# Esquema.net
KiCad netlist of a schematic drawn in Altium Designer
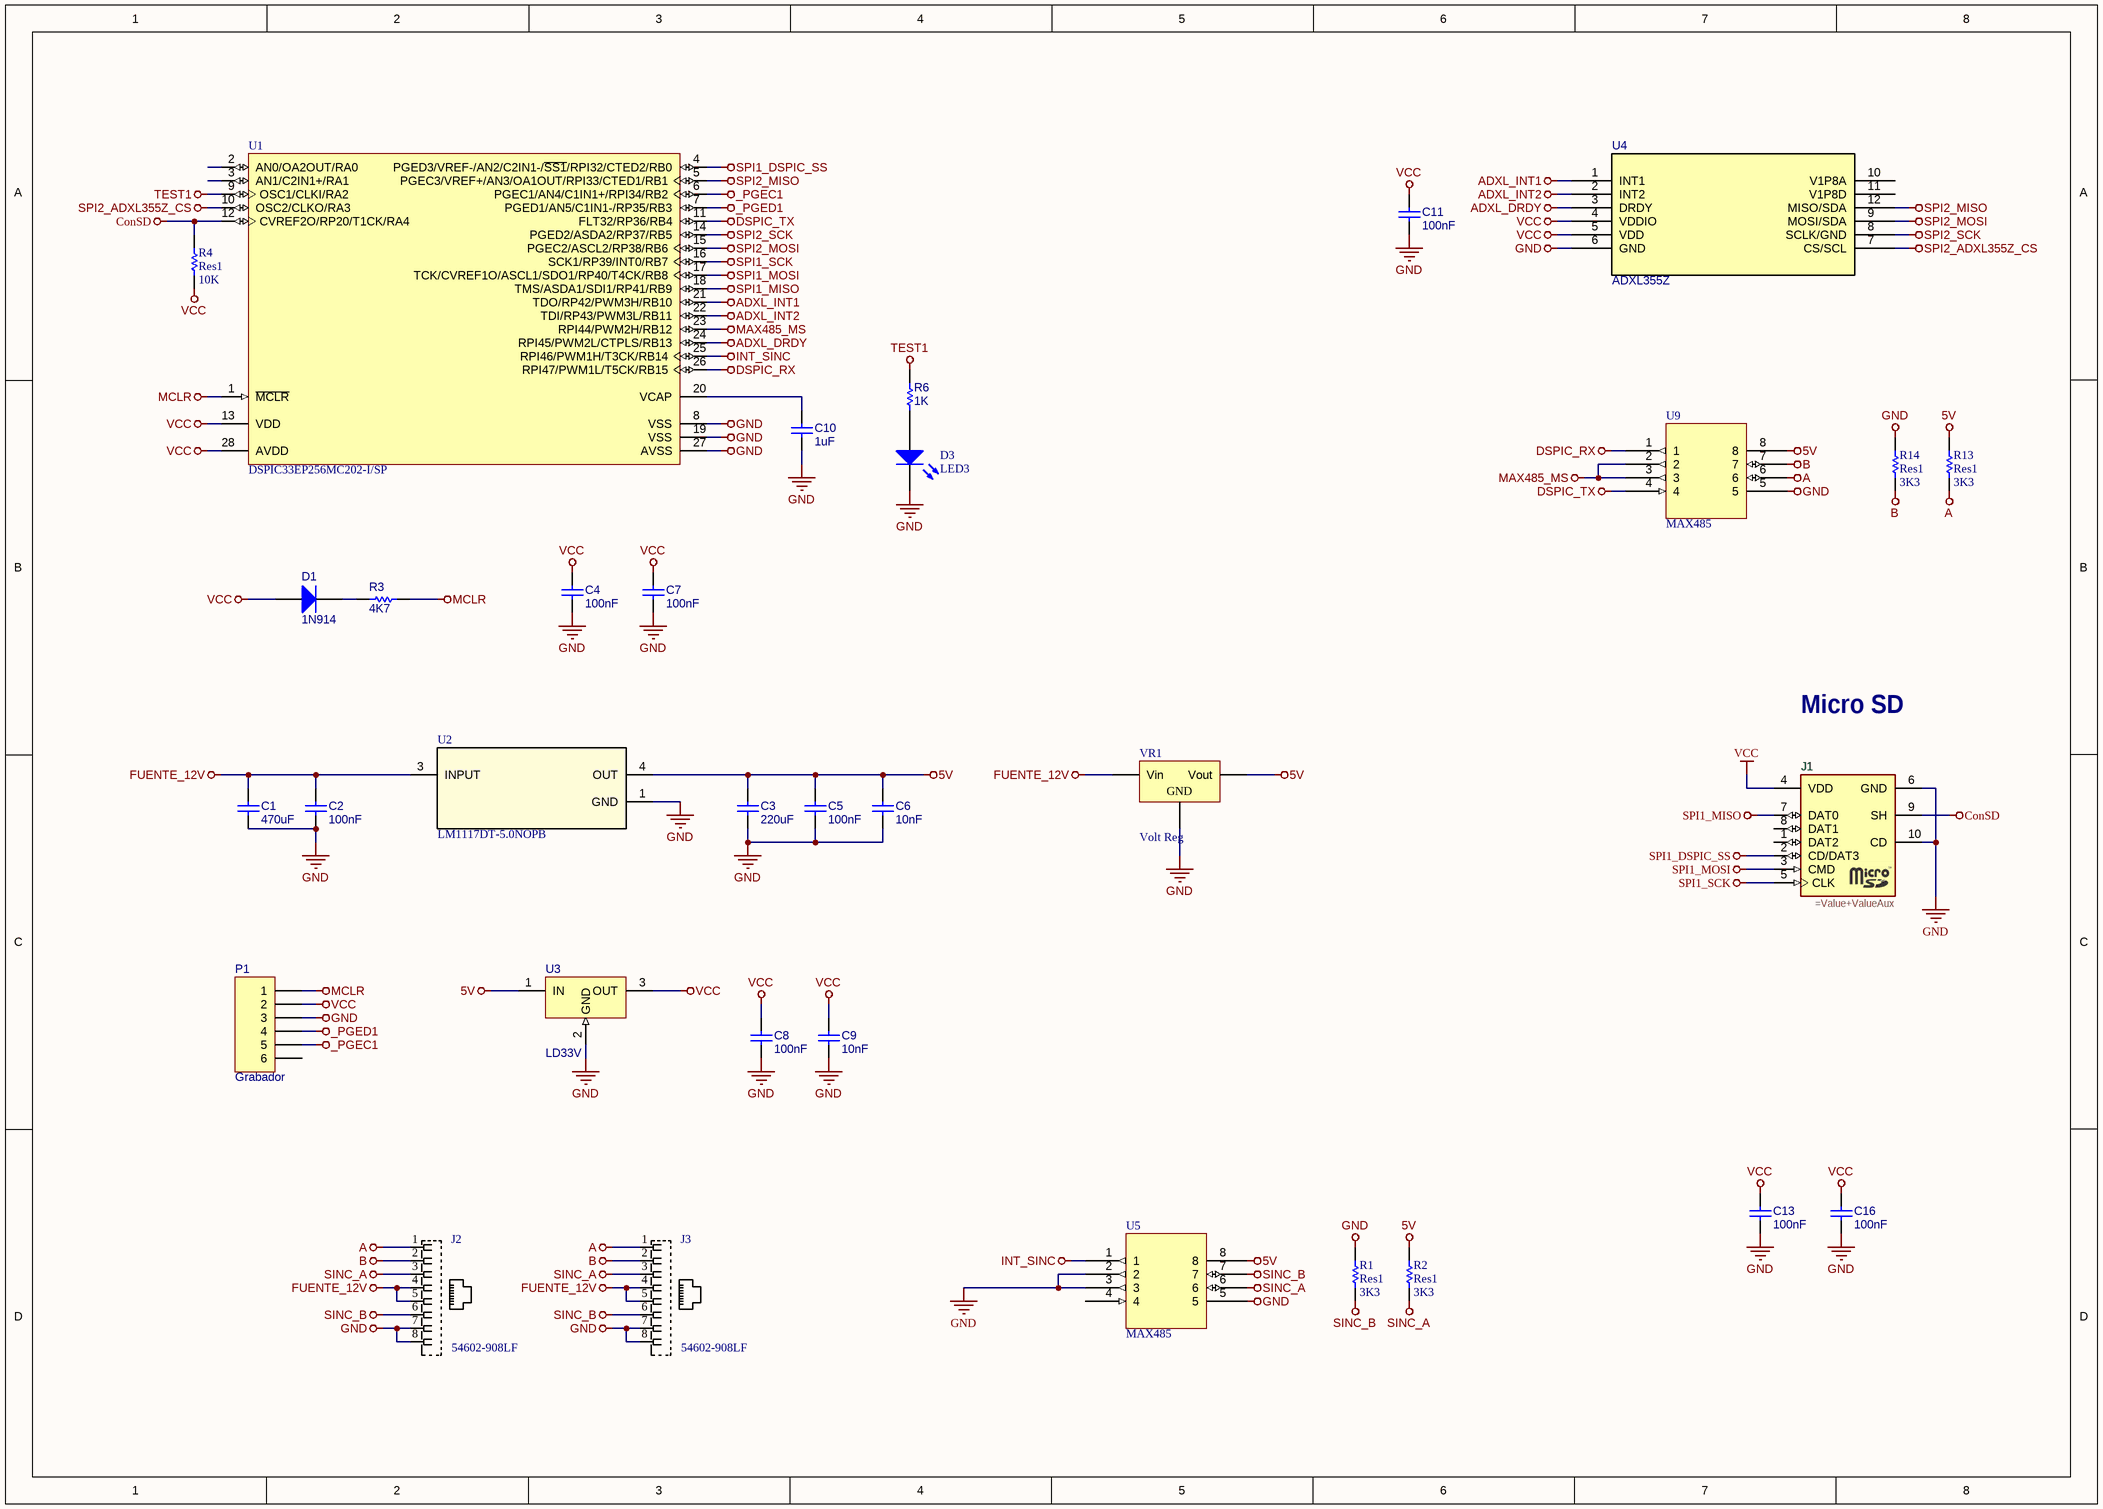
[diagram p0: Esquema.SchDoc]

(export (version "E")
  (design (tool "Eeschema 10.0.6"))
  (components
    (comp (ref "C1")
      (value "470uF")
      (footprint "C100UFB")
      (description "Capacitor")
      (fields (field (name "Comment") "Cap") (field (name "PUBLISHER") "Altium Limited"))
      (libsource (lib "Miscellaneous Devices") (part "Cap"))
    )
    (comp (ref "C2")
      (value "100nF")
      (footprint "RAD0.2")
      (description "Capacitor")
      (fields (field (name "Comment") "Cap") (field (name "PUBLISHER") "Altium Limited"))
      (libsource (lib "Miscellaneous Devices") (part "Cap"))
    )
    (comp (ref "C3")
      (value "220uF")
      (footprint "C100UFB")
      (description "Capacitor")
      (fields (field (name "Comment") "Cap") (field (name "PUBLISHER") "Altium Limited"))
      (libsource (lib "Miscellaneous Devices") (part "Cap"))
    )
    (comp (ref "C4")
      (value "100nF")
      (footprint "RAD0.2")
      (description "Capacitor")
      (fields (field (name "Comment") "Cap") (field (name "PUBLISHER") "Altium Limited"))
      (libsource (lib "Miscellaneous Devices") (part "Cap"))
    )
    (comp (ref "C5")
      (value "100nF")
      (footprint "RAD0.2")
      (description "Capacitor")
      (fields (field (name "Comment") "Cap") (field (name "PUBLISHER") "Altium Limited"))
      (libsource (lib "Miscellaneous Devices") (part "Cap"))
    )
    (comp (ref "C6")
      (value "10nF")
      (footprint "RAD0.2")
      (description "Capacitor")
      (fields (field (name "Comment") "Cap") (field (name "PUBLISHER") "Altium Limited"))
      (libsource (lib "Miscellaneous Devices") (part "Cap"))
    )
    (comp (ref "C7")
      (value "100nF")
      (footprint "RAD0.2")
      (description "Capacitor")
      (fields (field (name "Comment") "Cap") (field (name "PUBLISHER") "Altium Limited"))
      (libsource (lib "Miscellaneous Devices") (part "Cap"))
    )
    (comp (ref "C8")
      (value "100nF")
      (footprint "RAD0.2")
      (description "Capacitor")
      (fields (field (name "Comment") "Cap") (field (name "PUBLISHER") "Altium Limited"))
      (libsource (lib "Miscellaneous Devices") (part "Cap"))
    )
    (comp (ref "C9")
      (value "10nF")
      (footprint "RAD0.2")
      (description "Capacitor")
      (fields (field (name "Comment") "Cap") (field (name "PUBLISHER") "Altium Limited"))
      (libsource (lib "Miscellaneous Devices") (part "Cap"))
    )
    (comp (ref "C10")
      (value "1uF")
      (footprint "RAD0.2")
      (description "Capacitor")
      (fields (field (name "Comment") "Cap") (field (name "PUBLISHER") "Altium Limited"))
      (libsource (lib "Miscellaneous Devices") (part "Cap"))
    )
    (comp (ref "C11")
      (value "100nF")
      (footprint "RAD0.2")
      (description "Capacitor")
      (fields (field (name "Comment") "Cap") (field (name "PUBLISHER") "Altium Limited"))
      (libsource (lib "Miscellaneous Devices") (part "Cap"))
    )
    (comp (ref "C13")
      (value "100nF")
      (footprint "RAD0.2")
      (description "Capacitor")
      (fields (field (name "Comment") "Cap") (field (name "PUBLISHER") "Altium Limited"))
      (libsource (lib "Miscellaneous Devices") (part "Cap"))
    )
    (comp (ref "C16")
      (value "100nF")
      (footprint "RAD0.2")
      (description "Capacitor")
      (fields (field (name "Comment") "Cap") (field (name "PUBLISHER") "Altium Limited"))
      (libsource (lib "Miscellaneous Devices") (part "Cap"))
    )
    (comp (ref "D1")
      (value "1N914")
      (footprint "DO-35")
      (description "High Conductance Fast Diode")
      (fields (field (name "PUBLISHER") "Altium Limited"))
      (libsource (lib "Miscellaneous Devices") (part "Diode 1N914"))
    )
    (comp (ref "D3")
      (value "LED3")
      (footprint "LED2")
      (description "Typical BLUE SiC LED")
      (fields (field (name "PUBLISHER") "Altium Limited"))
      (libsource (lib "Miscellaneous Devices") (part "LED3"))
    )
    (comp (ref "J1")
      (value "~")
      (footprint "microSD")
      (description "=Description")
      (libsource (lib "MICROSD") (part "MICROSD"))
    )
    (comp (ref "J2")
      (value "54602-908LF")
      (footprint "Propia:RJ45_CONN8_2-908LF_AMP")
      (description "Jack Modular Connector 8p8c _RJ45, Ethernet_ 90Â° Angle _Right_ Unshielded Cat3")
      (fields (field (name "DIGI-KEY_PART_NUMBER") "609-1046-ND") (field (name "MF") "Amphenol ICC"))
      (libsource (lib "54602-908LF") (part "54602-908LF"))
    )
    (comp (ref "J3")
      (value "54602-908LF")
      (footprint "Propia:RJ45_CONN8_2-908LF_AMP")
      (description "Jack Modular Connector 8p8c _RJ45, Ethernet_ 90Â° Angle _Right_ Unshielded Cat3")
      (fields (field (name "DIGI-KEY_PART_NUMBER") "609-1046-ND") (field (name "MF") "Amphenol ICC"))
      (libsource (lib "54602-908LF") (part "54602-908LF"))
    )
    (comp (ref "P1")
      (value "Grabador")
      (footprint "HDR1X6")
      (description "Header, 6-Pin")
      (fields (field (name "PUBLISHER") "Altium Limited"))
      (libsource (lib "Miscellaneous Connectors") (part "Header 6"))
    )
    (comp (ref "R1")
      (value "Res1")
      (footprint "Propia:AXIAL-0.3")
      (description "Resistor")
      (fields (field (name "ALTIUM_VALUE") "3K3") (field (name "PUBLISHER") "Altium Limited"))
      (libsource (lib "Miscellaneous Devices") (part "Res1"))
    )
    (comp (ref "R2")
      (value "Res1")
      (footprint "Propia:AXIAL-0.3")
      (description "Resistor")
      (fields (field (name "ALTIUM_VALUE") "3K3") (field (name "PUBLISHER") "Altium Limited"))
      (libsource (lib "Miscellaneous Devices") (part "Res1"))
    )
    (comp (ref "R3")
      (value "4K7")
      (footprint "AXIAL-0.3")
      (description "Resistor")
      (fields (field (name "Comment") "Res1") (field (name "PUBLISHER") "Altium Limited"))
      (libsource (lib "Miscellaneous Devices") (part "Res1"))
    )
    (comp (ref "R4")
      (value "Res1")
      (footprint "Propia:AXIAL-0.3")
      (description "Resistor")
      (fields (field (name "ALTIUM_VALUE") "10K") (field (name "PUBLISHER") "Altium Limited"))
      (libsource (lib "Miscellaneous Devices") (part "Res1"))
    )
    (comp (ref "R6")
      (value "1K")
      (footprint "AXIAL-0.3")
      (description "Resistor")
      (fields (field (name "Comment") "Res1") (field (name "PUBLISHER") "Altium Limited"))
      (libsource (lib "Miscellaneous Devices") (part "Res1"))
    )
    (comp (ref "R13")
      (value "Res1")
      (footprint "AXIAL-0.3")
      (description "Resistor")
      (fields (field (name "ALTIUM_VALUE") "3K3") (field (name "PUBLISHER") "Altium Limited"))
      (libsource (lib "Miscellaneous Devices") (part "Res1"))
    )
    (comp (ref "R14")
      (value "Res1")
      (footprint "AXIAL-0.3")
      (description "Resistor")
      (fields (field (name "ALTIUM_VALUE") "3K3") (field (name "PUBLISHER") "Altium Limited"))
      (libsource (lib "Miscellaneous Devices") (part "Res1"))
    )
    (comp (ref "U1")
      (value "DSPIC33EP256MC202-I/SP")
      (footprint "MCHP-SPDIP-SP28")
      (fields (field (name "MANUFACTURER") "Microchip"))
      (libsource (lib "Microchip dsPIC33E") (part "DSPIC33EP256MC202-I/SP"))
    )
    (comp (ref "U2")
      (value "LM1117DT-5.0NOPB")
      (footprint "NDP0003B")
      (description "No Description Available")
      (libsource (lib "Schlib1") (part "LM1117DT-5.0NOPB"))
    )
    (comp (ref "U3") (value "LD33V") (footprint "SOT-223") (libsource (lib "LibreriaRSA") (part "LD33V")))
    (comp (ref "U4")
      (value "ADXL355Z")
      (footprint "ADXL355Z")
      (libsource (lib "Micelaneos") (part "ADXL355Z"))
    )
    (comp (ref "U5") (value "MAX485") (footprint "MAX485") (libsource (lib "Integrados") (part "MAX485")))
    (comp (ref "U9") (value "MAX485") (footprint "MAX485") (libsource (lib "Integrados") (part "MAX485")))
    (comp (ref "VR1")
      (value "Volt Reg")
      (footprint "TO-220V")
      (description "Voltage Regulator")
      (fields (field (name "PUBLISHER") "Altium Limited"))
      (libsource (lib "Miscellaneous Devices") (part "Volt Reg"))
    )
  )
  (nets
    (net (code "1") (name "5V") (class "Default")
      (node (ref "C3") (pin "1") (pinfunction "1_1") (pintype "passive"))
      (node (ref "C5") (pin "1") (pinfunction "1_1") (pintype "passive"))
      (node (ref "C6") (pin "1") (pinfunction "1_1") (pintype "passive"))
      (node (ref "R13") (pin "2") (pinfunction "2_2") (pintype "passive"))
      (node (ref "R2") (pin "2") (pinfunction "2_2") (pintype "passive"))
      (node (ref "U2") (pin "4") (pinfunction "OUT_4") (pintype "power_in"))
      (node (ref "U3") (pin "1") (pinfunction "IN_1") (pintype "power_in"))
      (node (ref "U5") (pin "8") (pinfunction "8_8") (pintype "power_in"))
      (node (ref "U9") (pin "8") (pinfunction "8_8") (pintype "power_in"))
      (node (ref "VR1") (pin "3") (pinfunction "Vout_3") (pintype "passive"))
    )
    (net (code "2") (name "A") (class "Default")
      (node (ref "J2") (pin "1") (pinfunction "1_1") (pintype "passive"))
      (node (ref "J3") (pin "1") (pinfunction "1_1") (pintype "passive"))
      (node (ref "R13") (pin "1") (pinfunction "1_1") (pintype "passive"))
      (node (ref "U9") (pin "6") (pinfunction "6_6") (pintype "bidirectional"))
    )
    (net (code "3") (name "ADXL_DRDY") (class "Default")
      (node (ref "U1") (pin "24") (pinfunction "RPI45/PWM2L/CTPLS/RB13_24") (pintype "bidirectional"))
      (node (ref "U4") (pin "3") (pinfunction "DRDY_3") (pintype "passive"))
    )
    (net (code "4") (name "ADXL_INT1") (class "Default")
      (node (ref "U1") (pin "21") (pinfunction "TDO/RP42/PWM3H/RB10_21") (pintype "bidirectional"))
      (node (ref "U4") (pin "1") (pinfunction "INT1_1") (pintype "passive"))
    )
    (net (code "5") (name "ADXL_INT2") (class "Default")
      (node (ref "U1") (pin "22") (pinfunction "TDI/RP43/PWM3L/RB11_22") (pintype "bidirectional"))
      (node (ref "U4") (pin "2") (pinfunction "INT2_2") (pintype "passive"))
    )
    (net (code "6") (name "B") (class "Default")
      (node (ref "J2") (pin "2") (pinfunction "2_2") (pintype "passive"))
      (node (ref "J3") (pin "2") (pinfunction "2_2") (pintype "passive"))
      (node (ref "R14") (pin "1") (pinfunction "1_1") (pintype "passive"))
      (node (ref "U9") (pin "7") (pinfunction "7_7") (pintype "bidirectional"))
    )
    (net (code "7") (name "ConSD") (class "Default")
      (node (ref "J1") (pin "9") (pinfunction "SH_9") (pintype "passive"))
      (node (ref "R4") (pin "2") (pinfunction "2_2") (pintype "passive"))
      (node (ref "U1") (pin "12") (pinfunction "CVREF2O/RP20/T1CK/RA4_12") (pintype "bidirectional"))
    )
    (net (code "8") (name "DSPIC_RX") (class "Default")
      (node (ref "U1") (pin "26") (pinfunction "RPI47/PWM1L/T5CK/RB15_26") (pintype "bidirectional"))
      (node (ref "U9") (pin "1") (pinfunction "1_1") (pintype "output"))
    )
    (net (code "9") (name "DSPIC_TX") (class "Default")
      (node (ref "U1") (pin "11") (pinfunction "FLT32/RP36/RB4_11") (pintype "bidirectional"))
      (node (ref "U9") (pin "4") (pinfunction "4_4") (pintype "input"))
    )
    (net (code "10") (name "FUENTE_12V") (class "Default")
      (node (ref "C1") (pin "1") (pinfunction "1_1") (pintype "passive"))
      (node (ref "C2") (pin "1") (pinfunction "1_1") (pintype "passive"))
      (node (ref "J2") (pin "4") (pinfunction "4_4") (pintype "passive"))
      (node (ref "J2") (pin "5") (pinfunction "5_5") (pintype "passive"))
      (node (ref "J3") (pin "4") (pinfunction "4_4") (pintype "passive"))
      (node (ref "J3") (pin "5") (pinfunction "5_5") (pintype "passive"))
      (node (ref "U2") (pin "3") (pinfunction "INPUT_3") (pintype "power_in"))
      (node (ref "VR1") (pin "1") (pinfunction "Vin_1") (pintype "passive"))
    )
    (net (code "11") (name "GND") (class "Default")
      (node (ref "C1") (pin "2") (pinfunction "2_2") (pintype "passive"))
      (node (ref "C10") (pin "2") (pinfunction "2_2") (pintype "passive"))
      (node (ref "C11") (pin "2") (pinfunction "2_2") (pintype "passive"))
      (node (ref "C13") (pin "2") (pinfunction "2_2") (pintype "passive"))
      (node (ref "C16") (pin "2") (pinfunction "2_2") (pintype "passive"))
      (node (ref "C2") (pin "2") (pinfunction "2_2") (pintype "passive"))
      (node (ref "C3") (pin "2") (pinfunction "2_2") (pintype "passive"))
      (node (ref "C4") (pin "2") (pinfunction "2_2") (pintype "passive"))
      (node (ref "C5") (pin "2") (pinfunction "2_2") (pintype "passive"))
      (node (ref "C6") (pin "2") (pinfunction "2_2") (pintype "passive"))
      (node (ref "C7") (pin "2") (pinfunction "2_2") (pintype "passive"))
      (node (ref "C8") (pin "2") (pinfunction "2_2") (pintype "passive"))
      (node (ref "C9") (pin "2") (pinfunction "2_2") (pintype "passive"))
      (node (ref "D3") (pin "2") (pinfunction "K_2") (pintype "passive"))
      (node (ref "J1") (pin "10") (pinfunction "CD_10") (pintype "passive"))
      (node (ref "J1") (pin "6") (pinfunction "GND_6") (pintype "power_in"))
      (node (ref "J2") (pin "7") (pinfunction "7_7") (pintype "passive"))
      (node (ref "J2") (pin "8") (pinfunction "8_8") (pintype "passive"))
      (node (ref "J3") (pin "7") (pinfunction "7_7") (pintype "passive"))
      (node (ref "J3") (pin "8") (pinfunction "8_8") (pintype "passive"))
      (node (ref "P1") (pin "3") (pinfunction "3_3") (pintype "passive"))
      (node (ref "R1") (pin "2") (pinfunction "2_2") (pintype "passive"))
      (node (ref "R14") (pin "2") (pinfunction "2_2") (pintype "passive"))
      (node (ref "U1") (pin "19") (pinfunction "VSS_19") (pintype "power_in"))
      (node (ref "U1") (pin "27") (pinfunction "AVSS_27") (pintype "power_in"))
      (node (ref "U1") (pin "8") (pinfunction "VSS_8") (pintype "power_in"))
      (node (ref "U2") (pin "1") (pinfunction "GND_1") (pintype "power_in"))
      (node (ref "U3") (pin "2") (pinfunction "GND_2") (pintype "input"))
      (node (ref "U4") (pin "6") (pinfunction "GND_6") (pintype "passive"))
      (node (ref "U5") (pin "2") (pinfunction "2_2") (pintype "output"))
      (node (ref "U5") (pin "3") (pinfunction "3_3") (pintype "output"))
      (node (ref "U5") (pin "5") (pinfunction "5_5") (pintype "power_in"))
      (node (ref "U9") (pin "5") (pinfunction "5_5") (pintype "power_in"))
      (node (ref "VR1") (pin "2") (pinfunction "GND_2") (pintype "passive"))
    )
    (net (code "12") (name "INT_SINC") (class "Default")
      (node (ref "U1") (pin "25") (pinfunction "RPI46/PWM1H/T3CK/RB14_25") (pintype "bidirectional"))
      (node (ref "U5") (pin "1") (pinfunction "1_1") (pintype "output"))
    )
    (net (code "13") (name "MAX485_MS") (class "Default")
      (node (ref "U1") (pin "23") (pinfunction "RPI44/PWM2H/RB12_23") (pintype "bidirectional"))
      (node (ref "U9") (pin "2") (pinfunction "2_2") (pintype "output"))
      (node (ref "U9") (pin "3") (pinfunction "3_3") (pintype "output"))
    )
    (net (code "14") (name "MCLR") (class "Default")
      (node (ref "P1") (pin "1") (pinfunction "1_1") (pintype "passive"))
      (node (ref "R3") (pin "1") (pinfunction "1_1") (pintype "passive"))
      (node (ref "U1") (pin "1") (pinfunction "~{MCLR}_1") (pintype "input"))
    )
    (net (code "15") (name "Net-(D1-K)") (class "Default")
      (node (ref "D1") (pin "2") (pinfunction "K_2") (pintype "passive"))
      (node (ref "R3") (pin "2") (pinfunction "2_2") (pintype "passive"))
    )
    (net (code "16") (name "Net-(D3-A)") (class "Default")
      (node (ref "D3") (pin "1") (pinfunction "A_1") (pintype "passive"))
      (node (ref "R6") (pin "2") (pinfunction "2_2") (pintype "passive"))
    )
    (net (code "17") (name "Net-(U1-VCAP)") (class "Default")
      (node (ref "C10") (pin "1") (pinfunction "1_1") (pintype "passive"))
      (node (ref "U1") (pin "20") (pinfunction "VCAP_20") (pintype "passive"))
    )
    (net (code "18") (name "SINC_A") (class "Default")
      (node (ref "J2") (pin "3") (pinfunction "3_3") (pintype "passive"))
      (node (ref "J3") (pin "3") (pinfunction "3_3") (pintype "passive"))
      (node (ref "R2") (pin "1") (pinfunction "1_1") (pintype "passive"))
      (node (ref "U5") (pin "6") (pinfunction "6_6") (pintype "bidirectional"))
    )
    (net (code "19") (name "SINC_B") (class "Default")
      (node (ref "J2") (pin "6") (pinfunction "6_6") (pintype "passive"))
      (node (ref "J3") (pin "6") (pinfunction "6_6") (pintype "passive"))
      (node (ref "R1") (pin "1") (pinfunction "1_1") (pintype "passive"))
      (node (ref "U5") (pin "7") (pinfunction "7_7") (pintype "bidirectional"))
    )
    (net (code "20") (name "SPI1_DSPIC_SS") (class "Default")
      (node (ref "J1") (pin "2") (pinfunction "CD/DAT3_2") (pintype "bidirectional"))
      (node (ref "U1") (pin "4") (pinfunction "PGED3/VREF-/AN2/C2IN1-/~{SS1}/RPI32/CTED2/RB0_4") (pintype "bidirectional"))
    )
    (net (code "21") (name "SPI1_MISO") (class "Default")
      (node (ref "J1") (pin "7") (pinfunction "DAT0_7") (pintype "bidirectional"))
      (node (ref "U1") (pin "18") (pinfunction "TMS/ASDA1/SDI1/RP41/RB9_18") (pintype "bidirectional"))
    )
    (net (code "22") (name "SPI1_MOSI") (class "Default")
      (node (ref "J1") (pin "3") (pinfunction "CMD_3") (pintype "input"))
      (node (ref "U1") (pin "17") (pinfunction "TCK/CVREF1O/ASCL1/SDO1/RP40/T4CK/RB8_17") (pintype "bidirectional"))
    )
    (net (code "23") (name "SPI1_SCK") (class "Default")
      (node (ref "J1") (pin "5") (pinfunction "CLK_5") (pintype "input"))
      (node (ref "U1") (pin "16") (pinfunction "SCK1/RP39/INT0/RB7_16") (pintype "bidirectional"))
    )
    (net (code "24") (name "SPI2_ADXL355Z_CS") (class "Default")
      (node (ref "U1") (pin "10") (pinfunction "OSC2/CLKO/RA3_10") (pintype "bidirectional"))
      (node (ref "U4") (pin "7") (pinfunction "CS/SCL_7") (pintype "passive"))
    )
    (net (code "25") (name "SPI2_MISO") (class "Default")
      (node (ref "U1") (pin "5") (pinfunction "PGEC3/VREF+/AN3/OA1OUT/RPI33/CTED1/RB1_5") (pintype "bidirectional"))
      (node (ref "U4") (pin "12") (pinfunction "MISO/SDA_12") (pintype "passive"))
    )
    (net (code "26") (name "SPI2_MOSI") (class "Default")
      (node (ref "U1") (pin "15") (pinfunction "PGEC2/ASCL2/RP38/RB6_15") (pintype "bidirectional"))
      (node (ref "U4") (pin "9") (pinfunction "MOSI/SDA_9") (pintype "passive"))
    )
    (net (code "27") (name "SPI2_SCK") (class "Default")
      (node (ref "U1") (pin "14") (pinfunction "PGED2/ASDA2/RP37/RB5_14") (pintype "bidirectional"))
      (node (ref "U4") (pin "8") (pinfunction "SCLK/GND_8") (pintype "passive"))
    )
    (net (code "28") (name "TEST1") (class "Default")
      (node (ref "R6") (pin "1") (pinfunction "1_1") (pintype "passive"))
      (node (ref "U1") (pin "9") (pinfunction "OSC1/CLKI/RA2_9") (pintype "bidirectional"))
    )
    (net (code "29") (name "VCC") (class "Default")
      (node (ref "C11") (pin "1") (pinfunction "1_1") (pintype "passive"))
      (node (ref "C13") (pin "1") (pinfunction "1_1") (pintype "passive"))
      (node (ref "C16") (pin "1") (pinfunction "1_1") (pintype "passive"))
      (node (ref "C4") (pin "1") (pinfunction "1_1") (pintype "passive"))
      (node (ref "C7") (pin "1") (pinfunction "1_1") (pintype "passive"))
      (node (ref "C8") (pin "1") (pinfunction "1_1") (pintype "passive"))
      (node (ref "C9") (pin "1") (pinfunction "1_1") (pintype "passive"))
      (node (ref "D1") (pin "1") (pinfunction "A_1") (pintype "passive"))
      (node (ref "J1") (pin "4") (pinfunction "VDD_4") (pintype "power_in"))
      (node (ref "P1") (pin "2") (pinfunction "2_2") (pintype "passive"))
      (node (ref "R4") (pin "1") (pinfunction "1_1") (pintype "passive"))
      (node (ref "U1") (pin "13") (pinfunction "VDD_13") (pintype "power_in"))
      (node (ref "U1") (pin "28") (pinfunction "AVDD_28") (pintype "power_in"))
      (node (ref "U3") (pin "3") (pinfunction "OUT_3") (pintype "power_in"))
      (node (ref "U4") (pin "4") (pinfunction "VDDIO_4") (pintype "passive"))
      (node (ref "U4") (pin "5") (pinfunction "VDD_5") (pintype "passive"))
    )
    (net (code "30") (name "_PGEC1") (class "Default")
      (node (ref "P1") (pin "5") (pinfunction "5_5") (pintype "passive"))
      (node (ref "U1") (pin "6") (pinfunction "PGEC1/AN4/C1IN1+/RPI34/RB2_6") (pintype "bidirectional"))
    )
    (net (code "31") (name "_PGED1") (class "Default")
      (node (ref "P1") (pin "4") (pinfunction "4_4") (pintype "passive"))
      (node (ref "U1") (pin "7") (pinfunction "PGED1/AN5/C1IN1-/RP35/RB3_7") (pintype "bidirectional"))
    )
    (net (code "32") (name "unconnected-(J1-DAT1-Pad8)") (class "Default")
      (node (ref "J1") (pin "8") (pinfunction "DAT1_8") (pintype "bidirectional"))
    )
    (net (code "33") (name "unconnected-(J1-DAT2-Pad1)") (class "Default")
      (node (ref "J1") (pin "1") (pinfunction "DAT2_1") (pintype "bidirectional"))
    )
    (net (code "34") (name "unconnected-(P1-Pad6)") (class "Default")
      (node (ref "P1") (pin "6") (pinfunction "6_6") (pintype "passive"))
    )
    (net (code "35") (name "unconnected-(U1-AN0{slash}OA2OUT{slash}RA0-Pad2)") (class "Default")
      (node (ref "U1") (pin "2") (pinfunction "AN0/OA2OUT/RA0_2") (pintype "bidirectional"))
    )
    (net (code "36") (name "unconnected-(U1-AN1{slash}C2IN1+{slash}RA1-Pad3)") (class "Default")
      (node (ref "U1") (pin "3") (pinfunction "AN1/C2IN1+/RA1_3") (pintype "bidirectional"))
    )
    (net (code "37") (name "unconnected-(U4-V1P8A-Pad10)") (class "Default")
      (node (ref "U4") (pin "10") (pinfunction "V1P8A_10") (pintype "passive"))
    )
    (net (code "38") (name "unconnected-(U4-V1P8D-Pad11)") (class "Default")
      (node (ref "U4") (pin "11") (pinfunction "V1P8D_11") (pintype "passive"))
    )
    (net (code "39") (name "unconnected-(U5-Pad4)") (class "Default")
      (node (ref "U5") (pin "4") (pinfunction "4_4") (pintype "input"))
    )
  )
)
